# 1-Schematic_Relay_5v_1.net
KiCad netlist of a schematic drawn in EasyEDA
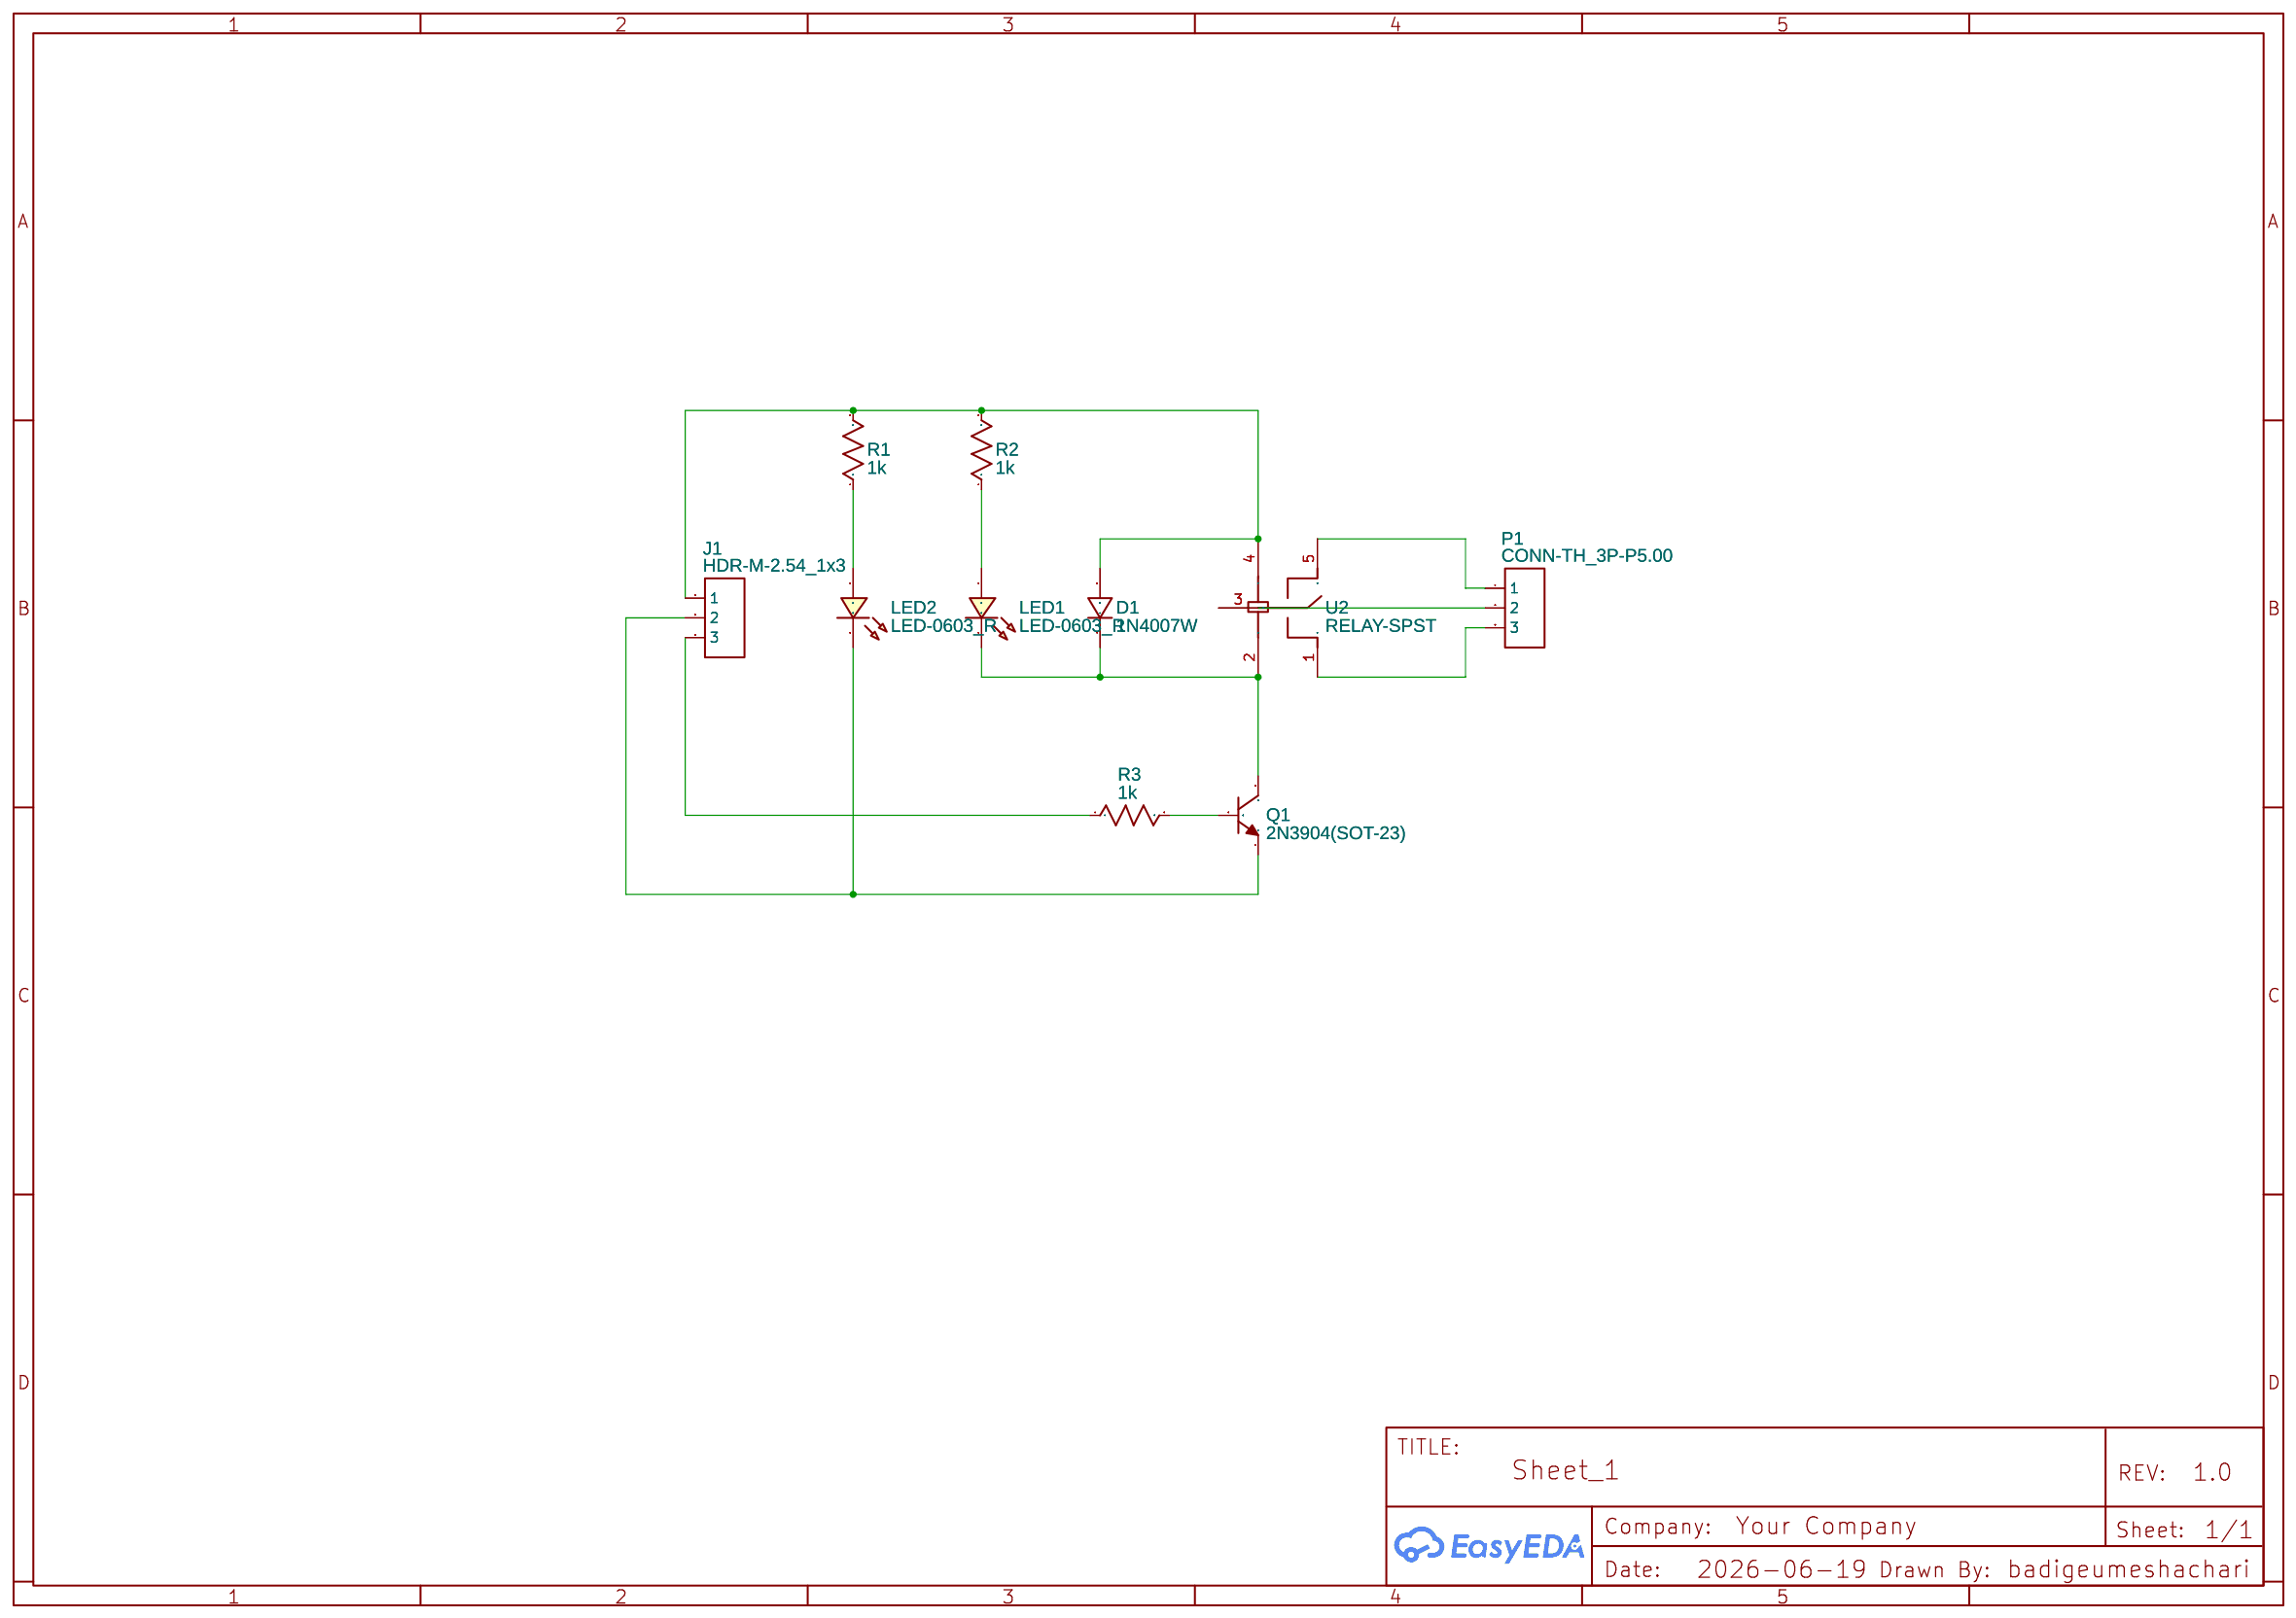
[diagram p0: schematic sheet]

(export (version "E")
  (design (tool "Eeschema 10.0.6"))
  (components
    (comp (ref "D1")
      (value "1N4007W")
      (fields (field (name "Manufacturer") "BLUE ROCKET"))
      (libsource (lib "") (part "1N4007W"))
    )
    (comp (ref "J1") (value "HDR-M-2.54_1x3") (libsource (lib "") (part "HDR-M-2.54_1x3")))
    (comp (ref "LED1")
      (value "LED-0603_R")
      (fields
        (field (name "Manufacturer Part") "19-217/R6C-AL1M2VY/3T")
        (field (name "Manufacturer") "EVERLIGHT(台湾亿光)")
      )
      (libsource (lib "") (part "LED-0603_R"))
    )
    (comp (ref "LED2")
      (value "LED-0603_R")
      (fields
        (field (name "Manufacturer Part") "19-217/R6C-AL1M2VY/3T")
        (field (name "Manufacturer") "EVERLIGHT(台湾亿光)")
      )
      (libsource (lib "") (part "LED-0603_R"))
    )
    (comp (ref "P1") (value "CONN-TH_3P-P5.00") (libsource (lib "") (part "CONN-TH_3P-P5.00")))
    (comp (ref "Q1")
      (value "2N3904(SOT-23)")
      (fields (field (name "Manufacturer Part") "2n3904S-RTK/PS") (field (name "Manufacturer") "KEC"))
      (libsource (lib "") (part "2N3904(SOT-23)"))
    )
    (comp (ref "R1") (value "1k") (libsource (lib "") (part "R_0603_US")))
    (comp (ref "R2") (value "1k") (libsource (lib "") (part "R_0603_US")))
    (comp (ref "R3") (value "1k") (libsource (lib "") (part "R_0603_US_1")))
    (comp (ref "U2")
      (value "RELAY-SPST")
      (fields (field (name "Manufacturer Part") "Relay-SPST"))
      (libsource (lib "") (part "RELAY-SPST"))
    )
  )
  (nets
    (net (code "1") (name "Net-(D1-Pad2)") (class "Default")
      (node (ref "D1") (pin "2") (pinfunction "2_2") (pintype "unspecified"))
      (node (ref "J1") (pin "1") (pinfunction "1_1") (pintype "input"))
      (node (ref "R1") (pin "2") (pinfunction "2_2") (pintype "unspecified"))
      (node (ref "R2") (pin "2") (pinfunction "2_2") (pintype "unspecified"))
      (node (ref "U2") (pin "4") (pinfunction "4_4") (pintype "unspecified"))
    )
    (net (code "2") (name "Net-(J1-Pad3)") (class "Default")
      (node (ref "J1") (pin "3") (pinfunction "3_3") (pintype "input"))
      (node (ref "R3") (pin "1") (pinfunction "1_1") (pintype "unspecified"))
    )
    (net (code "3") (name "Net-(LED1-Pad1)") (class "Default")
      (node (ref "LED1") (pin "1") (pinfunction "1_1") (pintype "unspecified"))
      (node (ref "R2") (pin "1") (pinfunction "1_1") (pintype "unspecified"))
    )
    (net (code "4") (name "Net-(LED2-Pad1)") (class "Default")
      (node (ref "LED2") (pin "1") (pinfunction "1_1") (pintype "unspecified"))
      (node (ref "R1") (pin "1") (pinfunction "1_1") (pintype "unspecified"))
    )
    (net (code "5") (name "Net-(P1-Pad1)") (class "Default")
      (node (ref "P1") (pin "1") (pinfunction "1_1") (pintype "unspecified"))
      (node (ref "U2") (pin "5") (pinfunction "5_5") (pintype "unspecified"))
    )
    (net (code "6") (name "Net-(P1-Pad2)") (class "Default")
      (node (ref "P1") (pin "2") (pinfunction "2_2") (pintype "unspecified"))
      (node (ref "U2") (pin "3") (pinfunction "3_3") (pintype "unspecified"))
    )
    (net (code "7") (name "Net-(P1-Pad3)") (class "Default")
      (node (ref "P1") (pin "3") (pinfunction "3_3") (pintype "unspecified"))
      (node (ref "U2") (pin "1") (pinfunction "1_1") (pintype "unspecified"))
    )
    (net (code "8") (name "Net-(Q1-B)") (class "Default")
      (node (ref "Q1") (pin "2") (pinfunction "B_2") (pintype "input"))
      (node (ref "R3") (pin "2") (pinfunction "2_2") (pintype "unspecified"))
    )
    (net (code "9") (name "Net-(Q1-C)") (class "Default")
      (node (ref "D1") (pin "1") (pinfunction "1_1") (pintype "unspecified"))
      (node (ref "LED1") (pin "2") (pinfunction "2_2") (pintype "unspecified"))
      (node (ref "Q1") (pin "3") (pinfunction "C_3") (pintype "input"))
      (node (ref "U2") (pin "2") (pinfunction "2_2") (pintype "unspecified"))
    )
    (net (code "10") (name "Net-(Q1-E)") (class "Default")
      (node (ref "J1") (pin "2") (pinfunction "2_2") (pintype "input"))
      (node (ref "LED2") (pin "2") (pinfunction "2_2") (pintype "unspecified"))
      (node (ref "Q1") (pin "1") (pinfunction "E_1") (pintype "input"))
    )
  )
)
